# myLEDBlinker.net
KiCad netlist of a schematic drawn in Altium Designer
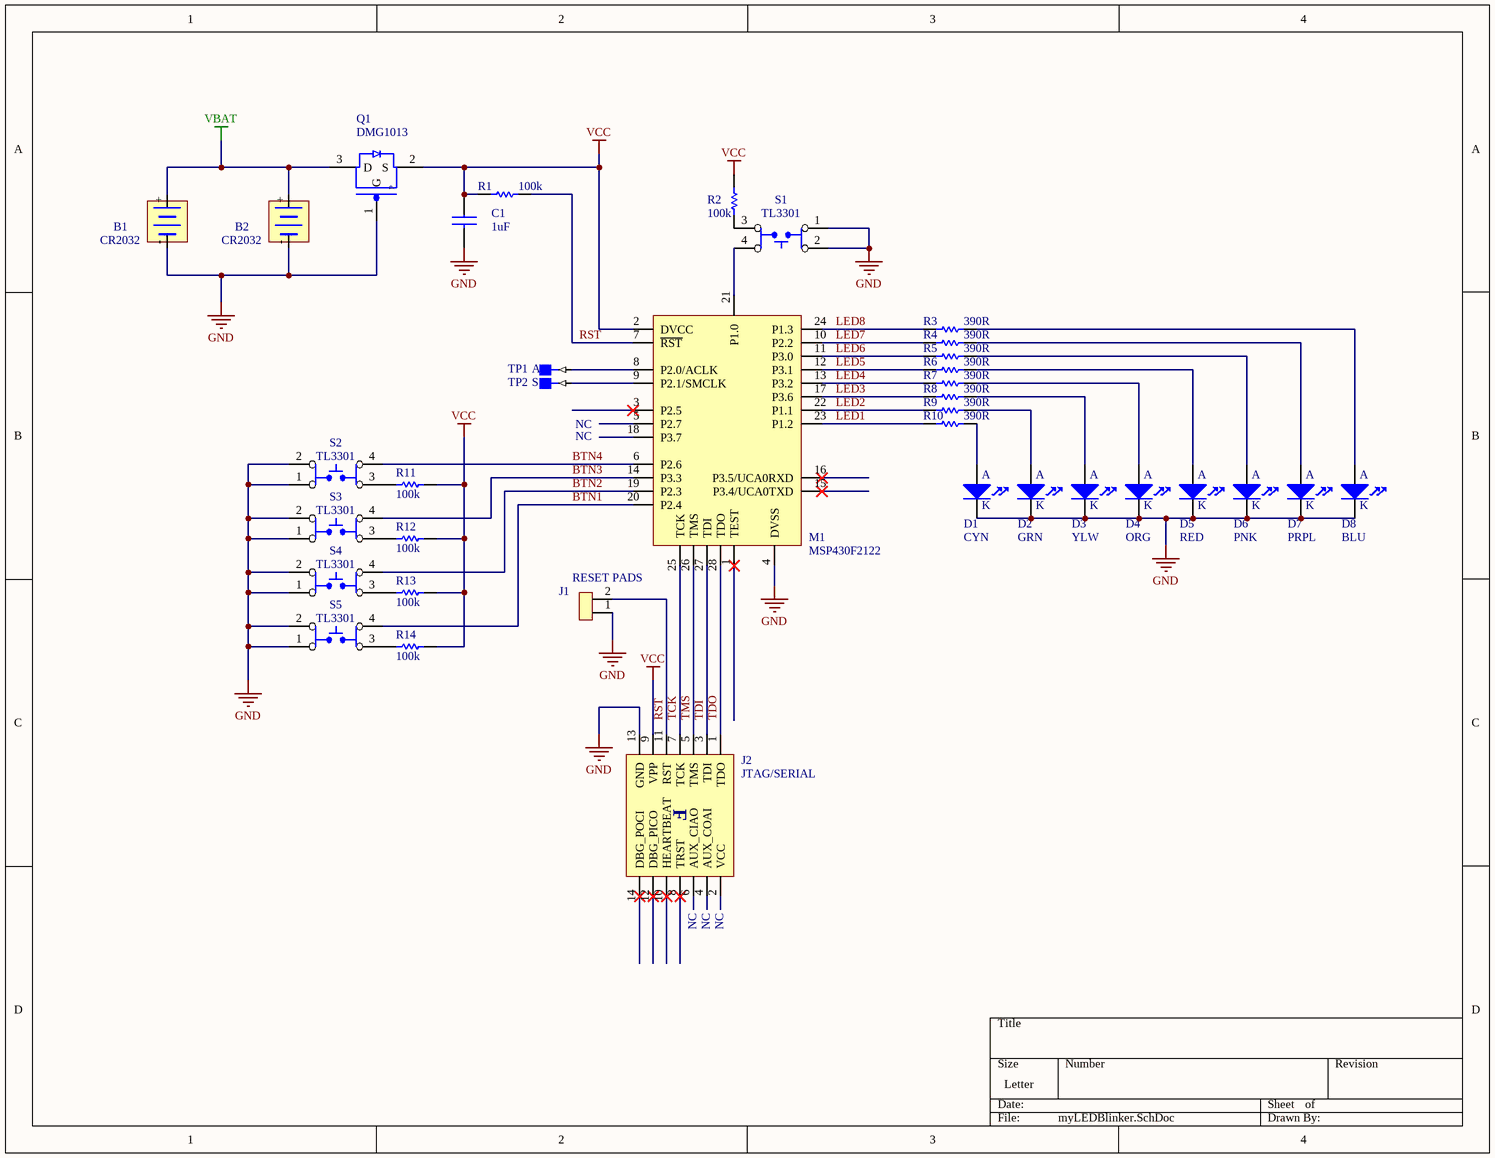
[diagram p0: myLEDBlinker.SchDoc]

(export (version "E")
  (design (tool "Eeschema 10.0.6"))
  (components
    (comp (ref "B1")
      (value "CR2032")
      (footprint "CONN BATTERY HOLDER CR2032")
      (description "3V Coincell Battery")
      (fields
        (field (name "3. MANUFACTURER PART NUMBER") "BK-912")
        (field (name "4. DIGI-KEY PART NUMBER") "BK-912-ND")
        (field (name "7. MODIFIED BY") "JRL")
      )
      (libsource (lib "Altium Example Master Schematic Library") (part "CONN BATTERY HOLDER CR2032"))
    )
    (comp (ref "B2")
      (value "CR2032")
      (footprint "CONN BATTERY HOLDER CR2032")
      (description "3V Coincell Battery")
      (fields
        (field (name "3. MANUFACTURER PART NUMBER") "BK-912")
        (field (name "4. DIGI-KEY PART NUMBER") "BK-912-ND")
        (field (name "7. MODIFIED BY") "JRL")
      )
      (libsource (lib "Altium Example Master Schematic Library") (part "CONN BATTERY HOLDER CR2032"))
    )
    (comp (ref "C1")
      (value "1uF")
      (footprint "0603")
      (fields (field (name "7. MODIFIED BY") "*"))
      (libsource (lib "Altium Example Master Schematic Library") (part "CAPACITOR NON-POLARIZED"))
    )
    (comp (ref "D1")
      (value "CYN")
      (footprint "PLCC-2 AK")
      (description "CYAN")
      (fields (field (name "7. MODIFIED BY") "*"))
      (libsource (lib "Altium Example Master Schematic Library") (part "LED AK"))
    )
    (comp (ref "D2")
      (value "GRN")
      (footprint "PLCC-2 AK")
      (description "GREEN")
      (fields (field (name "7. MODIFIED BY") "*"))
      (libsource (lib "Altium Example Master Schematic Library") (part "LED AK"))
    )
    (comp (ref "D3")
      (value "YLW")
      (footprint "PLCC-2 AK")
      (description "YELLOW")
      (fields (field (name "7. MODIFIED BY") "*"))
      (libsource (lib "Altium Example Master Schematic Library") (part "LED AK"))
    )
    (comp (ref "D4")
      (value "ORG")
      (footprint "PLCC-2 AK")
      (description "ORANGE")
      (fields (field (name "7. MODIFIED BY") "*"))
      (libsource (lib "Altium Example Master Schematic Library") (part "LED AK"))
    )
    (comp (ref "D5")
      (value "RED")
      (footprint "PLCC-2 AK")
      (fields (field (name "7. MODIFIED BY") "*"))
      (libsource (lib "Altium Example Master Schematic Library") (part "LED AK"))
    )
    (comp (ref "D6")
      (value "PNK")
      (footprint "PLCC-2 AK")
      (description "PINK")
      (fields (field (name "7. MODIFIED BY") "*"))
      (libsource (lib "Altium Example Master Schematic Library") (part "LED AK"))
    )
    (comp (ref "D7")
      (value "PRPL")
      (footprint "PLCC-2 AK")
      (description "PURPLE")
      (fields (field (name "7. MODIFIED BY") "*"))
      (libsource (lib "Altium Example Master Schematic Library") (part "LED AK"))
    )
    (comp (ref "D8")
      (value "BLU")
      (footprint "PLCC-2 AK")
      (description "BLUE")
      (fields (field (name "7. MODIFIED BY") "*"))
      (libsource (lib "Altium Example Master Schematic Library") (part "LED AK"))
    )
    (comp (ref "J1")
      (value "RESET PADS")
      (footprint "HDR1X2")
      (fields (field (name "7. MODIFIED BY") "*"))
      (libsource (lib "Altium Example Master Schematic Library") (part "CONN SIP 2"))
    )
    (comp (ref "J2")
      (value "JTAG/SERIAL")
      (footprint "CONN 14POS 7X2 SMT FEMALE SMALL")
      (fields
        (field (name "3. MANUFACTURER PART NUMBER") "20021321-00014T4LF")
        (field (name "4. DIGI-KEY PART NUMBER") "609-3771-ND")
        (field (name "5. INTERNAL PART NUMBER") "100254")
        (field (name "7. MODIFIED BY") "BJW")
      )
      (libsource (lib "Altium Example Master Schematic Library") (part "CONN JTAG/SERIAL FEMALE"))
    )
    (comp (ref "M1")
      (value "MSP430F2122")
      (footprint "TSSOP28")
      (fields
        (field (name "3. MANUFACTURER PART NUMBER") "MSP430F2122TPWR")
        (field (name "4. DIGI-KEY PART NUMBER") "296-23365-ND")
        (field (name "7. MODIFIED BY") "BJW")
      )
      (libsource (lib "Altium Example Master Schematic Library") (part "MCU MSP430F2122 TSSOP28"))
    )
    (comp (ref "Q1")
      (value "DMG1013")
      (footprint "SC-70-3")
      (fields (field (name "7. MODIFIED BY") "*"))
      (libsource (lib "Altium Example Master Schematic Library") (part "TRANS PMOS 1G 2S 3D"))
    )
    (comp (ref "R1")
      (value "100k")
      (footprint "0603")
      (fields (field (name "7. MODIFIED BY") "*"))
      (libsource (lib "Altium Example Master Schematic Library") (part "RESISTOR"))
    )
    (comp (ref "R2")
      (value "100k")
      (footprint "0603")
      (fields (field (name "7. MODIFIED BY") "*"))
      (libsource (lib "Altium Example Master Schematic Library") (part "RESISTOR"))
    )
    (comp (ref "R3")
      (value "390R")
      (footprint "0603")
      (fields (field (name "7. MODIFIED BY") "*"))
      (libsource (lib "Altium Example Master Schematic Library") (part "RESISTOR"))
    )
    (comp (ref "R4")
      (value "390R")
      (footprint "0603")
      (fields (field (name "7. MODIFIED BY") "*"))
      (libsource (lib "Altium Example Master Schematic Library") (part "RESISTOR"))
    )
    (comp (ref "R5")
      (value "390R")
      (footprint "0603")
      (fields (field (name "7. MODIFIED BY") "*"))
      (libsource (lib "Altium Example Master Schematic Library") (part "RESISTOR"))
    )
    (comp (ref "R6")
      (value "390R")
      (footprint "0603")
      (fields (field (name "7. MODIFIED BY") "*"))
      (libsource (lib "Altium Example Master Schematic Library") (part "RESISTOR"))
    )
    (comp (ref "R7")
      (value "390R")
      (footprint "0603")
      (fields (field (name "7. MODIFIED BY") "*"))
      (libsource (lib "Altium Example Master Schematic Library") (part "RESISTOR"))
    )
    (comp (ref "R8")
      (value "390R")
      (footprint "0603")
      (fields (field (name "7. MODIFIED BY") "*"))
      (libsource (lib "Altium Example Master Schematic Library") (part "RESISTOR"))
    )
    (comp (ref "R9")
      (value "390R")
      (footprint "0603")
      (fields (field (name "7. MODIFIED BY") "*"))
      (libsource (lib "Altium Example Master Schematic Library") (part "RESISTOR"))
    )
    (comp (ref "R10")
      (value "390R")
      (footprint "0603")
      (fields (field (name "7. MODIFIED BY") "*"))
      (libsource (lib "Altium Example Master Schematic Library") (part "RESISTOR"))
    )
    (comp (ref "R11")
      (value "100k")
      (footprint "0603")
      (fields (field (name "7. MODIFIED BY") "*"))
      (libsource (lib "Altium Example Master Schematic Library") (part "RESISTOR"))
    )
    (comp (ref "R12")
      (value "100k")
      (footprint "0603")
      (fields (field (name "7. MODIFIED BY") "*"))
      (libsource (lib "Altium Example Master Schematic Library") (part "RESISTOR"))
    )
    (comp (ref "R13")
      (value "100k")
      (footprint "0603")
      (fields (field (name "7. MODIFIED BY") "*"))
      (libsource (lib "Altium Example Master Schematic Library") (part "RESISTOR"))
    )
    (comp (ref "R14")
      (value "100k")
      (footprint "0603")
      (fields (field (name "7. MODIFIED BY") "*"))
      (libsource (lib "Altium Example Master Schematic Library") (part "RESISTOR"))
    )
    (comp (ref "S1")
      (value "TL3301")
      (footprint "SWITCH TACT SMT TL3301 J LEAD")
      (description "SPST TACT SWITCH")
      (fields (field (name "3. MANUFACTURER PART NUMBER") "TL3301xxx") (field (name "7. MODIFIED BY") "JRL"))
      (libsource (lib "Altium Example Master Schematic Library End") (part "SWITCH SPST TL3301 JLEAD"))
    )
    (comp (ref "S2")
      (value "TL3301")
      (footprint "SWITCH TACT SMT TL3301 J LEAD")
      (description "SPST TACT SWITCH")
      (fields (field (name "3. MANUFACTURER PART NUMBER") "TL3301xxx") (field (name "7. MODIFIED BY") "JRL"))
      (libsource (lib "Altium Example Master Schematic Library End") (part "SWITCH SPST TL3301 JLEAD"))
    )
    (comp (ref "S3")
      (value "TL3301")
      (footprint "SWITCH TACT SMT TL3301 J LEAD")
      (description "SPST TACT SWITCH")
      (fields (field (name "3. MANUFACTURER PART NUMBER") "TL3301xxx") (field (name "7. MODIFIED BY") "JRL"))
      (libsource (lib "Altium Example Master Schematic Library End") (part "SWITCH SPST TL3301 JLEAD"))
    )
    (comp (ref "S4")
      (value "TL3301")
      (footprint "SWITCH TACT SMT TL3301 J LEAD")
      (description "SPST TACT SWITCH")
      (fields (field (name "3. MANUFACTURER PART NUMBER") "TL3301xxx") (field (name "7. MODIFIED BY") "JRL"))
      (libsource (lib "Altium Example Master Schematic Library End") (part "SWITCH SPST TL3301 JLEAD"))
    )
    (comp (ref "S5")
      (value "TL3301")
      (footprint "SWITCH TACT SMT TL3301 J LEAD")
      (description "SPST TACT SWITCH")
      (fields (field (name "3. MANUFACTURER PART NUMBER") "TL3301xxx") (field (name "7. MODIFIED BY") "JRL"))
      (libsource (lib "Altium Example Master Schematic Library End") (part "SWITCH SPST TL3301 JLEAD"))
    )
    (comp (ref "TP1")
      (value "A")
      (footprint "TEST POINT SMT")
      (fields (field (name "7. MODIFIED BY") "JRL"))
      (libsource (lib "Altium Example Master Schematic Library") (part "TEST POINT SMT"))
    )
    (comp (ref "TP2")
      (value "S")
      (footprint "TEST POINT SMT")
      (fields (field (name "7. MODIFIED BY") "JRL"))
      (libsource (lib "Altium Example Master Schematic Library") (part "TEST POINT SMT"))
    )
  )
  (nets
    (net (code "1") (name "/BTN1") (class "Default")
      (node (ref "M1") (pin "20") (pinfunction "P2.4_20") (pintype "passive"))
      (node (ref "S5") (pin "4") (pinfunction "Y2_4") (pintype "passive"))
    )
    (net (code "2") (name "/BTN2") (class "Default")
      (node (ref "M1") (pin "19") (pinfunction "P2.3_19") (pintype "passive"))
      (node (ref "S4") (pin "4") (pinfunction "Y2_4") (pintype "passive"))
    )
    (net (code "3") (name "/BTN3") (class "Default")
      (node (ref "M1") (pin "14") (pinfunction "P3.3_14") (pintype "passive"))
      (node (ref "S3") (pin "4") (pinfunction "Y2_4") (pintype "passive"))
    )
    (net (code "4") (name "/BTN4") (class "Default")
      (node (ref "M1") (pin "6") (pinfunction "P2.6_6") (pintype "passive"))
      (node (ref "S2") (pin "4") (pinfunction "Y2_4") (pintype "passive"))
    )
    (net (code "5") (name "/LED1") (class "Default")
      (node (ref "M1") (pin "23") (pinfunction "P1.2_23") (pintype "passive"))
      (node (ref "R10") (pin "1") (pinfunction "1_1") (pintype "passive"))
    )
    (net (code "6") (name "/LED2") (class "Default")
      (node (ref "M1") (pin "22") (pinfunction "P1.1_22") (pintype "passive"))
      (node (ref "R9") (pin "1") (pinfunction "1_1") (pintype "passive"))
    )
    (net (code "7") (name "/LED3") (class "Default")
      (node (ref "M1") (pin "17") (pinfunction "P3.6_17") (pintype "passive"))
      (node (ref "R8") (pin "1") (pinfunction "1_1") (pintype "passive"))
    )
    (net (code "8") (name "/LED4") (class "Default")
      (node (ref "M1") (pin "13") (pinfunction "P3.2_13") (pintype "passive"))
      (node (ref "R7") (pin "1") (pinfunction "1_1") (pintype "passive"))
    )
    (net (code "9") (name "/LED5") (class "Default")
      (node (ref "M1") (pin "12") (pinfunction "P3.1_12") (pintype "passive"))
      (node (ref "R6") (pin "1") (pinfunction "1_1") (pintype "passive"))
    )
    (net (code "10") (name "/LED6") (class "Default")
      (node (ref "M1") (pin "11") (pinfunction "P3.0_11") (pintype "passive"))
      (node (ref "R5") (pin "1") (pinfunction "1_1") (pintype "passive"))
    )
    (net (code "11") (name "/LED7") (class "Default")
      (node (ref "M1") (pin "10") (pinfunction "P2.2_10") (pintype "passive"))
      (node (ref "R4") (pin "1") (pinfunction "1_1") (pintype "passive"))
    )
    (net (code "12") (name "/LED8") (class "Default")
      (node (ref "M1") (pin "24") (pinfunction "P1.3_24") (pintype "passive"))
      (node (ref "R3") (pin "1") (pinfunction "1_1") (pintype "passive"))
    )
    (net (code "13") (name "/RST") (class "Default")
      (node (ref "J1") (pin "2") (pintype "passive"))
      (node (ref "J2") (pin "11") (pinfunction "RST_11") (pintype "passive"))
      (node (ref "M1") (pin "7") (pinfunction "~{RST}_7") (pintype "passive"))
      (node (ref "R1") (pin "2") (pinfunction "2_2") (pintype "passive"))
    )
    (net (code "14") (name "/TCK") (class "Default")
      (node (ref "J2") (pin "7") (pinfunction "TCK_7") (pintype "passive"))
      (node (ref "M1") (pin "25") (pinfunction "TCK_25") (pintype "passive"))
    )
    (net (code "15") (name "/TDI") (class "Default")
      (node (ref "J2") (pin "3") (pinfunction "TDI_3") (pintype "passive"))
      (node (ref "M1") (pin "27") (pinfunction "TDI_27") (pintype "passive"))
    )
    (net (code "16") (name "/TDO") (class "Default")
      (node (ref "J2") (pin "1") (pinfunction "TDO_1") (pintype "passive"))
      (node (ref "M1") (pin "28") (pinfunction "TDO_28") (pintype "passive"))
    )
    (net (code "17") (name "/TMS") (class "Default")
      (node (ref "J2") (pin "5") (pinfunction "TMS_5") (pintype "passive"))
      (node (ref "M1") (pin "26") (pinfunction "TMS_26") (pintype "passive"))
    )
    (net (code "18") (name "GND") (class "Default")
      (node (ref "B1") (pin "-") (pintype "passive"))
      (node (ref "B2") (pin "-") (pintype "passive"))
      (node (ref "C1") (pin "2") (pinfunction "2_2") (pintype "passive"))
      (node (ref "D1") (pin "K") (pinfunction "K_K") (pintype "passive"))
      (node (ref "D2") (pin "K") (pinfunction "K_K") (pintype "passive"))
      (node (ref "D3") (pin "K") (pinfunction "K_K") (pintype "passive"))
      (node (ref "D4") (pin "K") (pinfunction "K_K") (pintype "passive"))
      (node (ref "D5") (pin "K") (pinfunction "K_K") (pintype "passive"))
      (node (ref "D6") (pin "K") (pinfunction "K_K") (pintype "passive"))
      (node (ref "D7") (pin "K") (pinfunction "K_K") (pintype "passive"))
      (node (ref "D8") (pin "K") (pinfunction "K_K") (pintype "passive"))
      (node (ref "J1") (pin "1") (pintype "passive"))
      (node (ref "J2") (pin "13") (pinfunction "GND_13") (pintype "passive"))
      (node (ref "M1") (pin "4") (pinfunction "DVSS_4") (pintype "passive"))
      (node (ref "Q1") (pin "1") (pinfunction "G_1") (pintype "passive"))
      (node (ref "S1") (pin "1") (pinfunction "X1_1") (pintype "passive"))
      (node (ref "S1") (pin "2") (pinfunction "X2_2") (pintype "passive"))
      (node (ref "S2") (pin "1") (pinfunction "X1_1") (pintype "passive"))
      (node (ref "S2") (pin "2") (pinfunction "X2_2") (pintype "passive"))
      (node (ref "S3") (pin "1") (pinfunction "X1_1") (pintype "passive"))
      (node (ref "S3") (pin "2") (pinfunction "X2_2") (pintype "passive"))
      (node (ref "S4") (pin "1") (pinfunction "X1_1") (pintype "passive"))
      (node (ref "S4") (pin "2") (pinfunction "X2_2") (pintype "passive"))
      (node (ref "S5") (pin "1") (pinfunction "X1_1") (pintype "passive"))
      (node (ref "S5") (pin "2") (pinfunction "X2_2") (pintype "passive"))
    )
    (net (code "19") (name "Net-(D1-PadA)") (class "Default")
      (node (ref "D1") (pin "A") (pinfunction "A_A") (pintype "passive"))
      (node (ref "R10") (pin "2") (pinfunction "2_2") (pintype "passive"))
    )
    (net (code "20") (name "Net-(D2-PadA)") (class "Default")
      (node (ref "D2") (pin "A") (pinfunction "A_A") (pintype "passive"))
      (node (ref "R9") (pin "2") (pinfunction "2_2") (pintype "passive"))
    )
    (net (code "21") (name "Net-(D3-PadA)") (class "Default")
      (node (ref "D3") (pin "A") (pinfunction "A_A") (pintype "passive"))
      (node (ref "R8") (pin "2") (pinfunction "2_2") (pintype "passive"))
    )
    (net (code "22") (name "Net-(D4-PadA)") (class "Default")
      (node (ref "D4") (pin "A") (pinfunction "A_A") (pintype "passive"))
      (node (ref "R7") (pin "2") (pinfunction "2_2") (pintype "passive"))
    )
    (net (code "23") (name "Net-(D5-PadA)") (class "Default")
      (node (ref "D5") (pin "A") (pinfunction "A_A") (pintype "passive"))
      (node (ref "R6") (pin "2") (pinfunction "2_2") (pintype "passive"))
    )
    (net (code "24") (name "Net-(D6-PadA)") (class "Default")
      (node (ref "D6") (pin "A") (pinfunction "A_A") (pintype "passive"))
      (node (ref "R5") (pin "2") (pinfunction "2_2") (pintype "passive"))
    )
    (net (code "25") (name "Net-(D7-PadA)") (class "Default")
      (node (ref "D7") (pin "A") (pinfunction "A_A") (pintype "passive"))
      (node (ref "R4") (pin "2") (pinfunction "2_2") (pintype "passive"))
    )
    (net (code "26") (name "Net-(D8-PadA)") (class "Default")
      (node (ref "D8") (pin "A") (pinfunction "A_A") (pintype "passive"))
      (node (ref "R3") (pin "2") (pinfunction "2_2") (pintype "passive"))
    )
    (net (code "27") (name "Net-(M1-P1.0)") (class "Default")
      (node (ref "M1") (pin "21") (pinfunction "P1.0_21") (pintype "passive"))
      (node (ref "S1") (pin "4") (pinfunction "Y2_4") (pintype "passive"))
    )
    (net (code "28") (name "Net-(M1-P2.0{slash}ACLK)") (class "Default")
      (node (ref "M1") (pin "8") (pinfunction "P2.0/ACLK_8") (pintype "passive"))
      (node (ref "TP1") (pin "1") (pinfunction "1_1") (pintype "input"))
    )
    (net (code "29") (name "Net-(M1-P2.1{slash}SMCLK)") (class "Default")
      (node (ref "M1") (pin "9") (pinfunction "P2.1/SMCLK_9") (pintype "passive"))
      (node (ref "TP2") (pin "1") (pinfunction "1_1") (pintype "input"))
    )
    (net (code "30") (name "Net-(S1-Y1)") (class "Default")
      (node (ref "R2") (pin "1") (pinfunction "1_1") (pintype "passive"))
      (node (ref "S1") (pin "3") (pinfunction "Y1_3") (pintype "passive"))
    )
    (net (code "31") (name "Net-(S2-Y1)") (class "Default")
      (node (ref "R11") (pin "2") (pinfunction "2_2") (pintype "passive"))
      (node (ref "S2") (pin "3") (pinfunction "Y1_3") (pintype "passive"))
    )
    (net (code "32") (name "Net-(S3-Y1)") (class "Default")
      (node (ref "R12") (pin "2") (pinfunction "2_2") (pintype "passive"))
      (node (ref "S3") (pin "3") (pinfunction "Y1_3") (pintype "passive"))
    )
    (net (code "33") (name "Net-(S4-Y1)") (class "Default")
      (node (ref "R13") (pin "2") (pinfunction "2_2") (pintype "passive"))
      (node (ref "S4") (pin "3") (pinfunction "Y1_3") (pintype "passive"))
    )
    (net (code "34") (name "Net-(S5-Y1)") (class "Default")
      (node (ref "R14") (pin "2") (pinfunction "2_2") (pintype "passive"))
      (node (ref "S5") (pin "3") (pinfunction "Y1_3") (pintype "passive"))
    )
    (net (code "35") (name "VBAT") (class "Default")
      (node (ref "B1") (pin "+") (pintype "passive"))
      (node (ref "B2") (pin "+") (pintype "passive"))
      (node (ref "Q1") (pin "3") (pinfunction "D_3") (pintype "passive"))
    )
    (net (code "36") (name "VCC") (class "Default")
      (node (ref "C1") (pin "1") (pinfunction "1_1") (pintype "passive"))
      (node (ref "J2") (pin "9") (pinfunction "VPP_9") (pintype "passive"))
      (node (ref "M1") (pin "2") (pinfunction "DVCC_2") (pintype "passive"))
      (node (ref "Q1") (pin "2") (pinfunction "S_2") (pintype "passive"))
      (node (ref "R1") (pin "1") (pinfunction "1_1") (pintype "passive"))
      (node (ref "R11") (pin "1") (pinfunction "1_1") (pintype "passive"))
      (node (ref "R12") (pin "1") (pinfunction "1_1") (pintype "passive"))
      (node (ref "R13") (pin "1") (pinfunction "1_1") (pintype "passive"))
      (node (ref "R14") (pin "1") (pinfunction "1_1") (pintype "passive"))
      (node (ref "R2") (pin "2") (pinfunction "2_2") (pintype "passive"))
    )
    (net (code "37") (name "unconnected-(J2-AUX_CIAO-Pad6)") (class "Default")
      (node (ref "J2") (pin "6") (pinfunction "AUX_CIAO_6") (pintype "passive"))
    )
    (net (code "38") (name "unconnected-(J2-AUX_COAI-Pad4)") (class "Default")
      (node (ref "J2") (pin "4") (pinfunction "AUX_COAI_4") (pintype "passive"))
    )
    (net (code "39") (name "unconnected-(J2-DBG_PICO-Pad12)") (class "Default")
      (node (ref "J2") (pin "12") (pinfunction "DBG_PICO_12") (pintype "passive+no_connect"))
    )
    (net (code "40") (name "unconnected-(J2-DBG_POCI-Pad14)") (class "Default")
      (node (ref "J2") (pin "14") (pinfunction "DBG_POCI_14") (pintype "passive+no_connect"))
    )
    (net (code "41") (name "unconnected-(J2-HEARTBEAT-Pad10)") (class "Default")
      (node (ref "J2") (pin "10") (pinfunction "HEARTBEAT_10") (pintype "passive+no_connect"))
    )
    (net (code "42") (name "unconnected-(J2-TRST-Pad8)") (class "Default")
      (node (ref "J2") (pin "8") (pinfunction "TRST_8") (pintype "passive+no_connect"))
    )
    (net (code "43") (name "unconnected-(J2-VCC-Pad2)") (class "Default")
      (node (ref "J2") (pin "2") (pinfunction "VCC_2") (pintype "passive"))
    )
    (net (code "44") (name "unconnected-(M1-P2.5-Pad3)") (class "Default")
      (node (ref "M1") (pin "3") (pinfunction "P2.5_3") (pintype "passive+no_connect"))
    )
    (net (code "45") (name "unconnected-(M1-P2.7-Pad5)") (class "Default")
      (node (ref "M1") (pin "5") (pinfunction "P2.7_5") (pintype "passive"))
    )
    (net (code "46") (name "unconnected-(M1-P3.4{slash}UCA0TXD-Pad15)") (class "Default")
      (node (ref "M1") (pin "15") (pinfunction "P3.4/UCA0TXD_15") (pintype "passive+no_connect"))
    )
    (net (code "47") (name "unconnected-(M1-P3.5{slash}UCA0RXD-Pad16)") (class "Default")
      (node (ref "M1") (pin "16") (pinfunction "P3.5/UCA0RXD_16") (pintype "passive+no_connect"))
    )
    (net (code "48") (name "unconnected-(M1-P3.7-Pad18)") (class "Default")
      (node (ref "M1") (pin "18") (pinfunction "P3.7_18") (pintype "passive"))
    )
    (net (code "49") (name "unconnected-(M1-TEST-Pad1)") (class "Default")
      (node (ref "M1") (pin "1") (pinfunction "TEST_1") (pintype "passive+no_connect"))
    )
  )
)
